# wheel.net
KiCad netlist of a schematic drawn in EAGLE
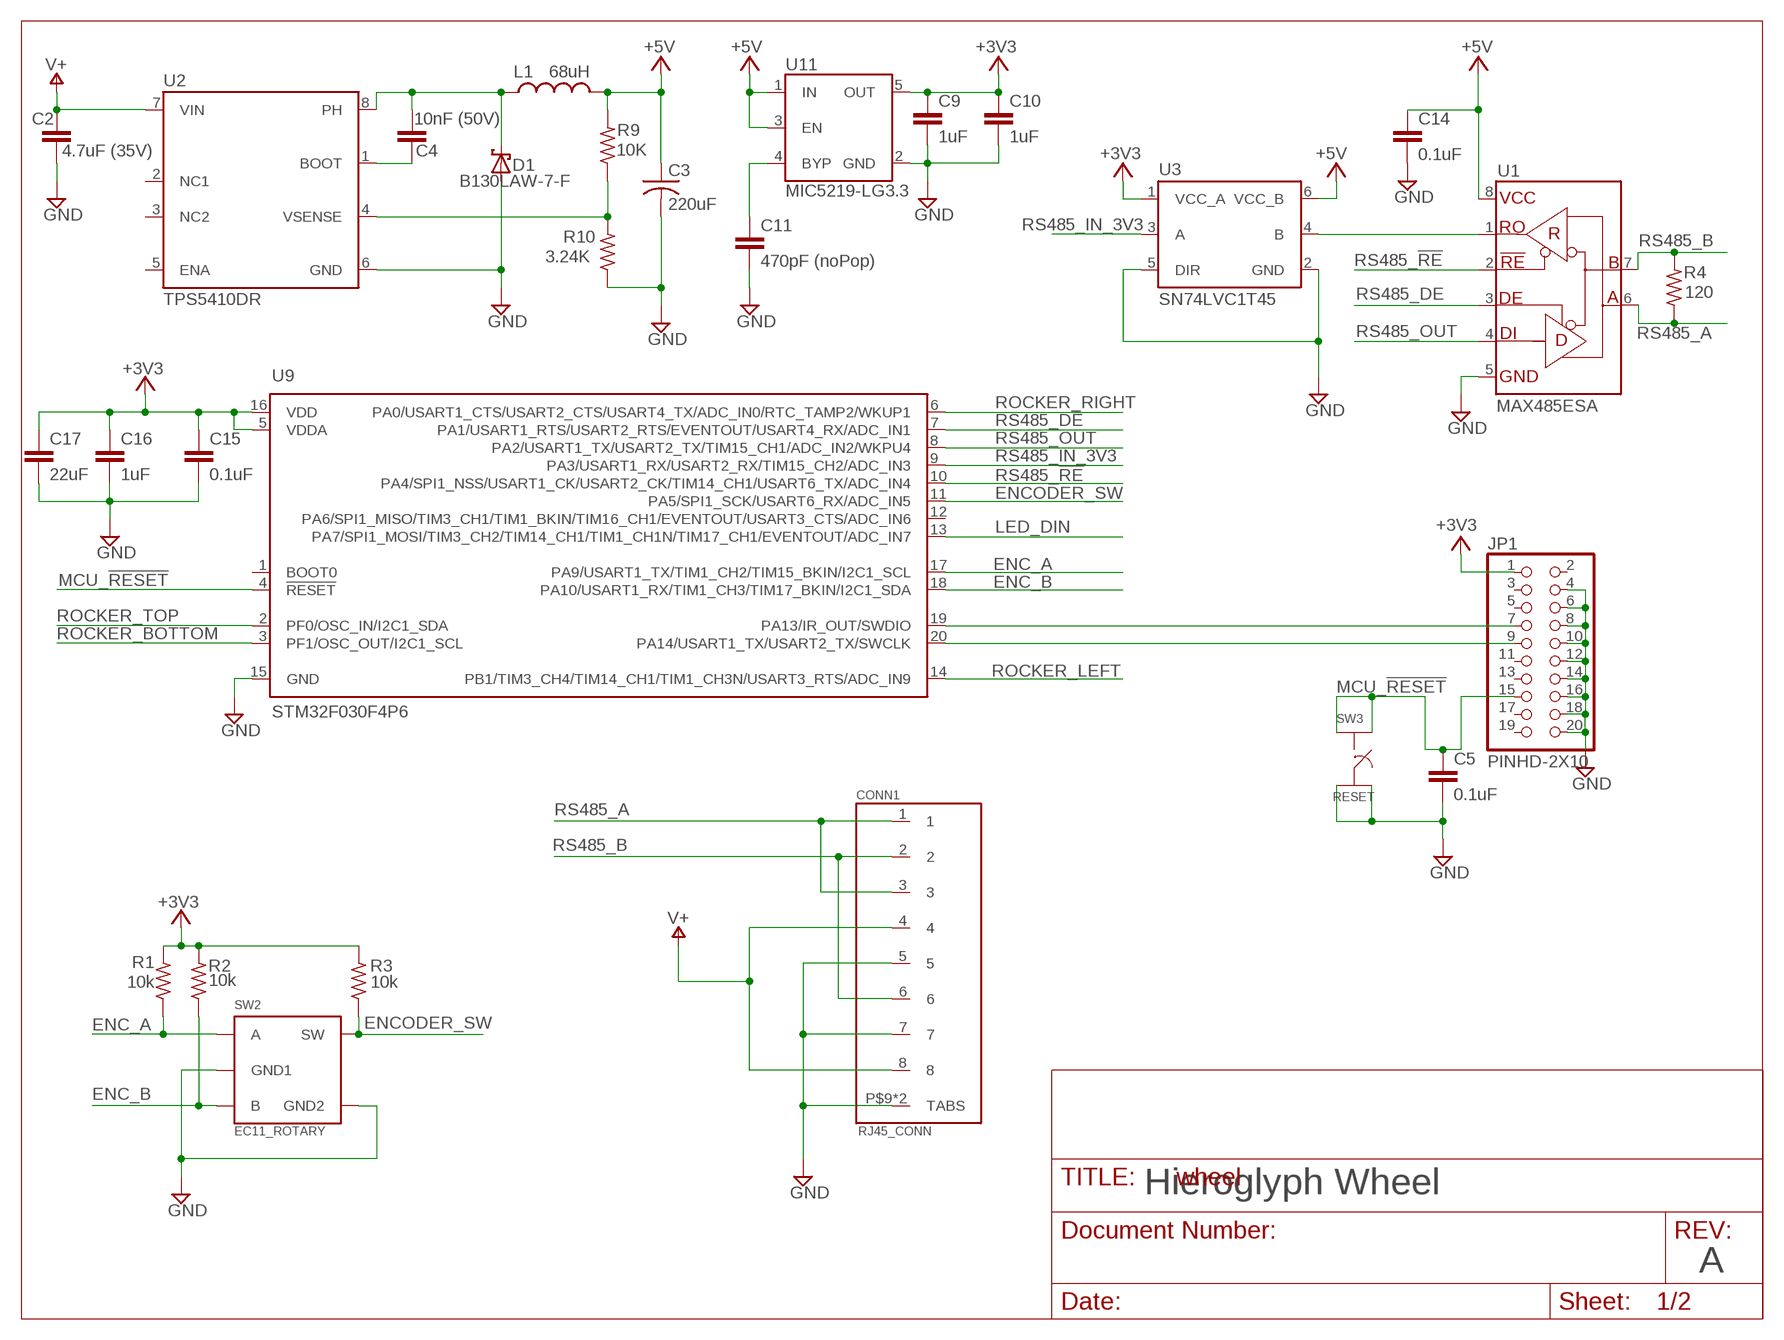
[diagram p0: schematic, sheet 1]
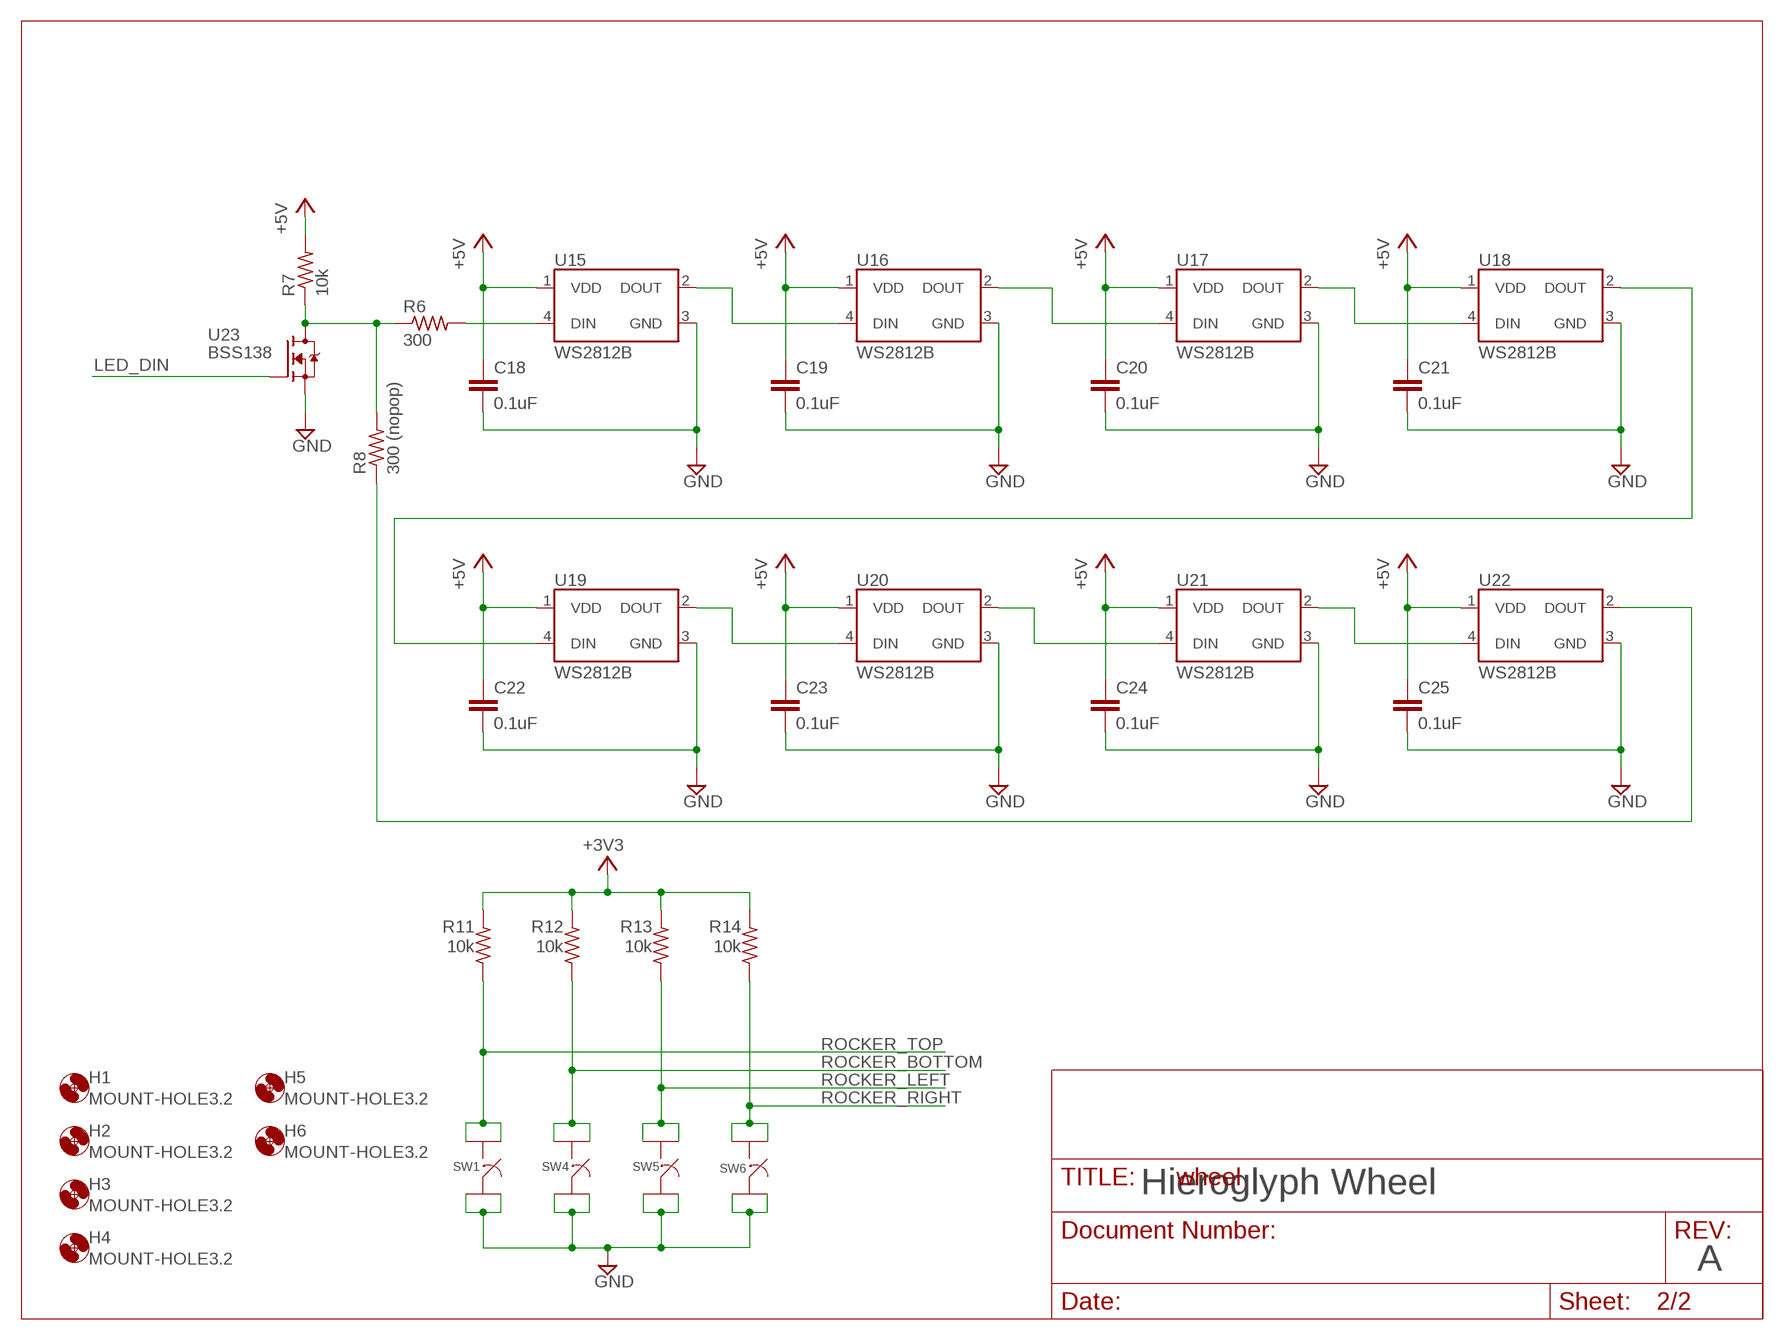
[diagram p1: schematic, sheet 2]

(export (version "E")
  (design (tool "Eeschema 10.0.6"))
  (components
    (comp (ref "C2")
      (value "4.7uF (35V)")
      (footprint "eagle-import:C0805")
      (libsource (lib "eagle-import") (part "C-EUC0805"))
    )
    (comp (ref "C3")
      (value "220uF")
      (footprint "eagle-import:KEMET_D_CAP")
      (libsource (lib "eagle-import") (part "TANT_CAP_D"))
    )
    (comp (ref "C4")
      (value "10nF (50V)")
      (footprint "eagle-import:C0805")
      (libsource (lib "eagle-import") (part "C-EUC0805"))
    )
    (comp (ref "C5")
      (value "0.1uF")
      (footprint "eagle-import:C0805")
      (libsource (lib "eagle-import") (part "C-EUC0805"))
    )
    (comp (ref "C9")
      (value "1uF")
      (footprint "eagle-import:C0805")
      (libsource (lib "eagle-import") (part "C-EUC0805"))
    )
    (comp (ref "C10")
      (value "1uF")
      (footprint "eagle-import:C0805")
      (libsource (lib "eagle-import") (part "C-EUC0805"))
    )
    (comp (ref "C11")
      (value "470pF (noPop)")
      (footprint "eagle-import:C0805")
      (libsource (lib "eagle-import") (part "C-EUC0805"))
    )
    (comp (ref "C14")
      (value "0.1uF")
      (footprint "eagle-import:C0805")
      (libsource (lib "eagle-import") (part "C-EUC0805"))
    )
    (comp (ref "C15")
      (value "0.1uF")
      (footprint "eagle-import:C0805")
      (libsource (lib "eagle-import") (part "C-EUC0805"))
    )
    (comp (ref "C16")
      (value "1uF")
      (footprint "eagle-import:C0805")
      (libsource (lib "eagle-import") (part "C-EUC0805"))
    )
    (comp (ref "C17")
      (value "22uF")
      (footprint "eagle-import:C0805")
      (libsource (lib "eagle-import") (part "C-EUC0805"))
    )
    (comp (ref "CONN1")
      (value "RJ45_CONN")
      (footprint "eagle-import:RJ45_VERT")
      (libsource (lib "eagle-import") (part "RJ45_CONN"))
    )
    (comp (ref "D1")
      (value "B130LAW-7-F")
      (footprint "eagle-import:SOD123")
      (libsource (lib "eagle-import") (part "B130LAW-7-F"))
    )
    (comp (ref "JP1")
      (value "PINHD-2X10")
      (footprint "eagle-import:2X10_W_KEY")
      (libsource (lib "eagle-import") (part "PINHD-2X10"))
    )
    (comp (ref "L1")
      (value "68uH")
      (footprint "eagle-import:CDRH127R")
      (libsource (lib "eagle-import") (part "L_CDRH127"))
    )
    (comp (ref "R1")
      (value "10k")
      (footprint "eagle-import:R0805")
      (libsource (lib "eagle-import") (part "R-US_R0805"))
    )
    (comp (ref "R2")
      (value "10k")
      (footprint "eagle-import:R0805")
      (libsource (lib "eagle-import") (part "R-US_R0805"))
    )
    (comp (ref "R3")
      (value "10k")
      (footprint "eagle-import:R0805")
      (libsource (lib "eagle-import") (part "R-US_R0805"))
    )
    (comp (ref "R4")
      (value "120")
      (footprint "eagle-import:R0805")
      (libsource (lib "eagle-import") (part "R-US_R0805"))
    )
    (comp (ref "R9")
      (value "10K")
      (footprint "eagle-import:R0805")
      (libsource (lib "eagle-import") (part "R-US_R0805"))
    )
    (comp (ref "R10")
      (value "3.24K")
      (footprint "eagle-import:R0805")
      (libsource (lib "eagle-import") (part "R-US_R0805"))
    )
    (comp (ref "SW2")
      (value "EC11_ROTARY")
      (footprint "eagle-import:EC11_ROTARY")
      (libsource (lib "eagle-import") (part "EC11_ROTARY"))
    )
    (comp (ref "SW3")
      (value "RESET")
      (footprint "eagle-import:MOM_SWITCH")
      (libsource (lib "eagle-import") (part "MOM_SWITCH"))
    )
    (comp (ref "U1")
      (value "MAX485ESA")
      (footprint "eagle-import:SO08")
      (libsource (lib "eagle-import") (part "MAX485ESA"))
    )
    (comp (ref "U2")
      (value "TPS5410DR")
      (footprint "eagle-import:SO08")
      (libsource (lib "eagle-import") (part "TPS5410DR"))
    )
    (comp (ref "U3")
      (value "SN74LVC1T45")
      (footprint "eagle-import:SOT23-6")
      (libsource (lib "eagle-import") (part "SN74LVC1T45"))
    )
    (comp (ref "U9")
      (value "STM32F030F4P6")
      (footprint "eagle-import:TSSOP20")
      (libsource (lib "eagle-import") (part "STM32F030F4P6"))
    )
    (comp (ref "U11")
      (value "MIC5219-LG3.3")
      (footprint "eagle-import:SOT23-5")
      (libsource (lib "eagle-import") (part "MIC5219XX"))
    )
    (comp (ref "C18")
      (value "0.1uF")
      (footprint "eagle-import:C0805")
      (libsource (lib "eagle-import") (part "C-EUC0805"))
    )
    (comp (ref "C19")
      (value "0.1uF")
      (footprint "eagle-import:C0805")
      (libsource (lib "eagle-import") (part "C-EUC0805"))
    )
    (comp (ref "C20")
      (value "0.1uF")
      (footprint "eagle-import:C0805")
      (libsource (lib "eagle-import") (part "C-EUC0805"))
    )
    (comp (ref "C21")
      (value "0.1uF")
      (footprint "eagle-import:C0805")
      (libsource (lib "eagle-import") (part "C-EUC0805"))
    )
    (comp (ref "C22")
      (value "0.1uF")
      (footprint "eagle-import:C0805")
      (libsource (lib "eagle-import") (part "C-EUC0805"))
    )
    (comp (ref "C23")
      (value "0.1uF")
      (footprint "eagle-import:C0805")
      (libsource (lib "eagle-import") (part "C-EUC0805"))
    )
    (comp (ref "C24")
      (value "0.1uF")
      (footprint "eagle-import:C0805")
      (libsource (lib "eagle-import") (part "C-EUC0805"))
    )
    (comp (ref "C25")
      (value "0.1uF")
      (footprint "eagle-import:C0805")
      (libsource (lib "eagle-import") (part "C-EUC0805"))
    )
    (comp (ref "H1")
      (value "MOUNT-HOLE3.2")
      (footprint "eagle-import:3,2")
      (libsource (lib "eagle-import") (part "MOUNT-HOLE3.2"))
    )
    (comp (ref "H2")
      (value "MOUNT-HOLE3.2")
      (footprint "eagle-import:3,2")
      (libsource (lib "eagle-import") (part "MOUNT-HOLE3.2"))
    )
    (comp (ref "H3")
      (value "MOUNT-HOLE3.2")
      (footprint "eagle-import:3,2")
      (libsource (lib "eagle-import") (part "MOUNT-HOLE3.2"))
    )
    (comp (ref "H4")
      (value "MOUNT-HOLE3.2")
      (footprint "eagle-import:3,2")
      (libsource (lib "eagle-import") (part "MOUNT-HOLE3.2"))
    )
    (comp (ref "H5")
      (value "MOUNT-HOLE3.2")
      (footprint "eagle-import:3,2")
      (libsource (lib "eagle-import") (part "MOUNT-HOLE3.2"))
    )
    (comp (ref "H6")
      (value "MOUNT-HOLE3.2")
      (footprint "eagle-import:3,2")
      (libsource (lib "eagle-import") (part "MOUNT-HOLE3.2"))
    )
    (comp (ref "R6")
      (value "300")
      (footprint "eagle-import:R0805")
      (libsource (lib "eagle-import") (part "R-US_R0805"))
    )
    (comp (ref "R7")
      (value "10k")
      (footprint "eagle-import:R0805")
      (libsource (lib "eagle-import") (part "R-US_R0805"))
    )
    (comp (ref "R8")
      (value "300 (nopop)")
      (footprint "eagle-import:R0805")
      (libsource (lib "eagle-import") (part "R-US_R0805"))
    )
    (comp (ref "R11")
      (value "10k")
      (footprint "eagle-import:R0805")
      (libsource (lib "eagle-import") (part "R-US_R0805"))
    )
    (comp (ref "R12")
      (value "10k")
      (footprint "eagle-import:R0805")
      (libsource (lib "eagle-import") (part "R-US_R0805"))
    )
    (comp (ref "R13")
      (value "10k")
      (footprint "eagle-import:R0805")
      (libsource (lib "eagle-import") (part "R-US_R0805"))
    )
    (comp (ref "R14")
      (value "10k")
      (footprint "eagle-import:R0805")
      (libsource (lib "eagle-import") (part "R-US_R0805"))
    )
    (comp (ref "SW1")
      (value "MOM_SWITCH")
      (footprint "eagle-import:MOM_SWITCH")
      (libsource (lib "eagle-import") (part "MOM_SWITCH"))
    )
    (comp (ref "SW4")
      (value "MOM_SWITCH")
      (footprint "eagle-import:MOM_SWITCH")
      (libsource (lib "eagle-import") (part "MOM_SWITCH"))
    )
    (comp (ref "SW5")
      (value "MOM_SWITCH")
      (footprint "eagle-import:MOM_SWITCH")
      (libsource (lib "eagle-import") (part "MOM_SWITCH"))
    )
    (comp (ref "SW6")
      (value "MOM_SWITCH")
      (footprint "eagle-import:MOM_SWITCH")
      (libsource (lib "eagle-import") (part "MOM_SWITCH"))
    )
    (comp (ref "U15")
      (value "WS2812B")
      (footprint "eagle-import:WS2812B")
      (libsource (lib "eagle-import") (part "WS2812B"))
    )
    (comp (ref "U16")
      (value "WS2812B")
      (footprint "eagle-import:WS2812B")
      (libsource (lib "eagle-import") (part "WS2812B"))
    )
    (comp (ref "U17")
      (value "WS2812B")
      (footprint "eagle-import:WS2812B")
      (libsource (lib "eagle-import") (part "WS2812B"))
    )
    (comp (ref "U18")
      (value "WS2812B")
      (footprint "eagle-import:WS2812B")
      (libsource (lib "eagle-import") (part "WS2812B"))
    )
    (comp (ref "U19")
      (value "WS2812B")
      (footprint "eagle-import:WS2812B")
      (libsource (lib "eagle-import") (part "WS2812B"))
    )
    (comp (ref "U20")
      (value "WS2812B")
      (footprint "eagle-import:WS2812B")
      (libsource (lib "eagle-import") (part "WS2812B"))
    )
    (comp (ref "U21")
      (value "WS2812B")
      (footprint "eagle-import:WS2812B")
      (libsource (lib "eagle-import") (part "WS2812B"))
    )
    (comp (ref "U22")
      (value "WS2812B")
      (footprint "eagle-import:WS2812B")
      (libsource (lib "eagle-import") (part "WS2812B"))
    )
    (comp (ref "U23")
      (value "BSS138")
      (footprint "eagle-import:SOT23")
      (libsource (lib "eagle-import") (part "BSS138"))
    )
  )
  (nets
    (net (code "1") (name "+3V3") (class "Default")
      (node (ref "C10") (pin "1") (pinfunction "1_1") (pintype "passive"))
      (node (ref "C15") (pin "1") (pinfunction "1_1") (pintype "passive"))
      (node (ref "C16") (pin "1") (pinfunction "1_1") (pintype "passive"))
      (node (ref "C17") (pin "1") (pinfunction "1_1") (pintype "passive"))
      (node (ref "C9") (pin "1") (pinfunction "1_1") (pintype "passive"))
      (node (ref "JP1") (pin "1") (pinfunction "1_1") (pintype "passive"))
      (node (ref "R1") (pin "2") (pinfunction "2_2") (pintype "passive"))
      (node (ref "R11") (pin "2") (pinfunction "2_2") (pintype "passive"))
      (node (ref "R12") (pin "2") (pinfunction "2_2") (pintype "passive"))
      (node (ref "R13") (pin "2") (pinfunction "2_2") (pintype "passive"))
      (node (ref "R14") (pin "2") (pinfunction "2_2") (pintype "passive"))
      (node (ref "R2") (pin "2") (pinfunction "2_2") (pintype "passive"))
      (node (ref "R3") (pin "2") (pinfunction "2_2") (pintype "passive"))
      (node (ref "U11") (pin "5") (pinfunction "OUT_5") (pintype "power_in"))
      (node (ref "U3") (pin "1") (pinfunction "VCC_A_1") (pintype "power_in"))
      (node (ref "U9") (pin "16") (pinfunction "VDD_16") (pintype "power_in"))
      (node (ref "U9") (pin "5") (pinfunction "VDDA_5") (pintype "power_in"))
    )
    (net (code "2") (name "+5V") (class "Default")
      (node (ref "C14") (pin "1") (pinfunction "1_1") (pintype "passive"))
      (node (ref "C18") (pin "1") (pinfunction "1_1") (pintype "passive"))
      (node (ref "C19") (pin "1") (pinfunction "1_1") (pintype "passive"))
      (node (ref "C20") (pin "1") (pinfunction "1_1") (pintype "passive"))
      (node (ref "C21") (pin "1") (pinfunction "1_1") (pintype "passive"))
      (node (ref "C22") (pin "1") (pinfunction "1_1") (pintype "passive"))
      (node (ref "C23") (pin "1") (pinfunction "1_1") (pintype "passive"))
      (node (ref "C24") (pin "1") (pinfunction "1_1") (pintype "passive"))
      (node (ref "C25") (pin "1") (pinfunction "1_1") (pintype "passive"))
      (node (ref "C3") (pin "+") (pinfunction "1_+") (pintype "passive"))
      (node (ref "L1") (pin "P$2") (pinfunction "2_P$2") (pintype "passive"))
      (node (ref "R7") (pin "2") (pinfunction "2_2") (pintype "passive"))
      (node (ref "R9") (pin "2") (pinfunction "2_2") (pintype "passive"))
      (node (ref "U1") (pin "8") (pinfunction "VCC_8") (pintype "power_in"))
      (node (ref "U11") (pin "1") (pinfunction "IN_1") (pintype "power_in"))
      (node (ref "U11") (pin "3") (pinfunction "EN_3") (pintype "input"))
      (node (ref "U15") (pin "1") (pinfunction "VDD_1") (pintype "power_in"))
      (node (ref "U16") (pin "1") (pinfunction "VDD_1") (pintype "power_in"))
      (node (ref "U17") (pin "1") (pinfunction "VDD_1") (pintype "power_in"))
      (node (ref "U18") (pin "1") (pinfunction "VDD_1") (pintype "power_in"))
      (node (ref "U19") (pin "1") (pinfunction "VDD_1") (pintype "power_in"))
      (node (ref "U20") (pin "1") (pinfunction "VDD_1") (pintype "power_in"))
      (node (ref "U21") (pin "1") (pinfunction "VDD_1") (pintype "power_in"))
      (node (ref "U22") (pin "1") (pinfunction "VDD_1") (pintype "power_in"))
      (node (ref "U3") (pin "6") (pinfunction "VCC_B_6") (pintype "power_in"))
    )
    (net (code "3") (name "ENCODER_SW") (class "Default")
      (node (ref "R3") (pin "1") (pinfunction "1_1") (pintype "passive"))
      (node (ref "SW2") (pin "SW") (pinfunction "SW_SW") (pintype "bidirectional"))
      (node (ref "U9") (pin "11") (pinfunction "PA5/SPI1_SCK/USART6_RX/ADC_IN5_11") (pintype "bidirectional"))
    )
    (net (code "4") (name "ENC_A") (class "Default")
      (node (ref "R1") (pin "1") (pinfunction "1_1") (pintype "passive"))
      (node (ref "SW2") (pin "A") (pinfunction "A_A") (pintype "bidirectional"))
      (node (ref "U9") (pin "17") (pinfunction "PA9/USART1_TX/TIM1_CH2/TIM15_BKIN/I2C1_SCL_17") (pintype "bidirectional"))
    )
    (net (code "5") (name "ENC_B") (class "Default")
      (node (ref "R2") (pin "1") (pinfunction "1_1") (pintype "passive"))
      (node (ref "SW2") (pin "B") (pinfunction "B_B") (pintype "bidirectional"))
      (node (ref "U9") (pin "18") (pinfunction "PA10/USART1_RX/TIM1_CH3/TIM17_BKIN/I2C1_SDA_18") (pintype "bidirectional"))
    )
    (net (code "6") (name "GND") (class "Default")
      (node (ref "C10") (pin "2") (pinfunction "2_2") (pintype "passive"))
      (node (ref "C11") (pin "2") (pinfunction "2_2") (pintype "passive"))
      (node (ref "C14") (pin "2") (pinfunction "2_2") (pintype "passive"))
      (node (ref "C15") (pin "2") (pinfunction "2_2") (pintype "passive"))
      (node (ref "C16") (pin "2") (pinfunction "2_2") (pintype "passive"))
      (node (ref "C17") (pin "2") (pinfunction "2_2") (pintype "passive"))
      (node (ref "C18") (pin "2") (pinfunction "2_2") (pintype "passive"))
      (node (ref "C19") (pin "2") (pinfunction "2_2") (pintype "passive"))
      (node (ref "C2") (pin "2") (pinfunction "2_2") (pintype "passive"))
      (node (ref "C20") (pin "2") (pinfunction "2_2") (pintype "passive"))
      (node (ref "C21") (pin "2") (pinfunction "2_2") (pintype "passive"))
      (node (ref "C22") (pin "2") (pinfunction "2_2") (pintype "passive"))
      (node (ref "C23") (pin "2") (pinfunction "2_2") (pintype "passive"))
      (node (ref "C24") (pin "2") (pinfunction "2_2") (pintype "passive"))
      (node (ref "C25") (pin "2") (pinfunction "2_2") (pintype "passive"))
      (node (ref "C3") (pin "-") (pinfunction "2_-") (pintype "passive"))
      (node (ref "C5") (pin "2") (pinfunction "2_2") (pintype "passive"))
      (node (ref "C9") (pin "2") (pinfunction "2_2") (pintype "passive"))
      (node (ref "CONN1") (pin "5") (pinfunction "5_5") (pintype "bidirectional"))
      (node (ref "CONN1") (pin "7") (pinfunction "7_7") (pintype "bidirectional"))
      (node (ref "CONN1") (pin "P$10") (pinfunction "TABS_P$10") (pintype "bidirectional"))
      (node (ref "CONN1") (pin "P$9") (pinfunction "TABS_P$9") (pintype "bidirectional"))
      (node (ref "D1") (pin "A") (pinfunction "A_A") (pintype "passive"))
      (node (ref "JP1") (pin "10") (pinfunction "10_10") (pintype "passive"))
      (node (ref "JP1") (pin "12") (pinfunction "12_12") (pintype "passive"))
      (node (ref "JP1") (pin "14") (pinfunction "14_14") (pintype "passive"))
      (node (ref "JP1") (pin "16") (pinfunction "16_16") (pintype "passive"))
      (node (ref "JP1") (pin "18") (pinfunction "18_18") (pintype "passive"))
      (node (ref "JP1") (pin "20") (pinfunction "20_20") (pintype "passive"))
      (node (ref "JP1") (pin "4") (pinfunction "4_4") (pintype "passive"))
      (node (ref "JP1") (pin "6") (pinfunction "6_6") (pintype "passive"))
      (node (ref "JP1") (pin "8") (pinfunction "8_8") (pintype "passive"))
      (node (ref "R10") (pin "1") (pinfunction "1_1") (pintype "passive"))
      (node (ref "SW1") (pin "P$3") (pinfunction "3_P$3") (pintype "bidirectional"))
      (node (ref "SW1") (pin "P$4") (pinfunction "4_P$4") (pintype "bidirectional"))
      (node (ref "SW2") (pin "C") (pinfunction "GND1_C") (pintype "bidirectional"))
      (node (ref "SW2") (pin "D") (pinfunction "GND2_D") (pintype "bidirectional"))
      (node (ref "SW3") (pin "P$3") (pinfunction "3_P$3") (pintype "bidirectional"))
      (node (ref "SW3") (pin "P$4") (pinfunction "4_P$4") (pintype "bidirectional"))
      (node (ref "SW4") (pin "P$3") (pinfunction "3_P$3") (pintype "bidirectional"))
      (node (ref "SW4") (pin "P$4") (pinfunction "4_P$4") (pintype "bidirectional"))
      (node (ref "SW5") (pin "P$3") (pinfunction "3_P$3") (pintype "bidirectional"))
      (node (ref "SW5") (pin "P$4") (pinfunction "4_P$4") (pintype "bidirectional"))
      (node (ref "SW6") (pin "P$3") (pinfunction "3_P$3") (pintype "bidirectional"))
      (node (ref "SW6") (pin "P$4") (pinfunction "4_P$4") (pintype "bidirectional"))
      (node (ref "U1") (pin "5") (pinfunction "GND_5") (pintype "power_in"))
      (node (ref "U11") (pin "2") (pinfunction "GND_2") (pintype "power_in"))
      (node (ref "U15") (pin "3") (pinfunction "GND_3") (pintype "power_in"))
      (node (ref "U16") (pin "3") (pinfunction "GND_3") (pintype "power_in"))
      (node (ref "U17") (pin "3") (pinfunction "GND_3") (pintype "power_in"))
      (node (ref "U18") (pin "3") (pinfunction "GND_3") (pintype "power_in"))
      (node (ref "U19") (pin "3") (pinfunction "GND_3") (pintype "power_in"))
      (node (ref "U2") (pin "6") (pinfunction "GND_6") (pintype "bidirectional"))
      (node (ref "U20") (pin "3") (pinfunction "GND_3") (pintype "power_in"))
      (node (ref "U21") (pin "3") (pinfunction "GND_3") (pintype "power_in"))
      (node (ref "U22") (pin "3") (pinfunction "GND_3") (pintype "power_in"))
      (node (ref "U23") (pin "2") (pinfunction "S_2") (pintype "passive"))
      (node (ref "U3") (pin "2") (pinfunction "GND_2") (pintype "power_in"))
      (node (ref "U3") (pin "5") (pinfunction "DIR_5") (pintype "input"))
      (node (ref "U9") (pin "15") (pinfunction "GND_15") (pintype "power_in"))
    )
    (net (code "7") (name "LED_DIN") (class "Default")
      (node (ref "U23") (pin "1") (pinfunction "G_1") (pintype "passive"))
      (node (ref "U9") (pin "13") (pinfunction "PA7/SPI1_MOSI/TIM3_CH2/TIM14_CH1/TIM1_CH1N/TIM17_CH1/EVENTOUT/ADC_IN7_13") (pintype "bidirectional"))
    )
    (net (code "8") (name "MCU_~{RESET}") (class "Default")
      (node (ref "C5") (pin "1") (pinfunction "1_1") (pintype "passive"))
      (node (ref "JP1") (pin "15") (pinfunction "15_15") (pintype "passive"))
      (node (ref "SW3") (pin "P$1") (pinfunction "1_P$1") (pintype "bidirectional"))
      (node (ref "SW3") (pin "P$2") (pinfunction "2_P$2") (pintype "bidirectional"))
      (node (ref "U9") (pin "4") (pinfunction "~{RESET}_4") (pintype "input"))
    )
    (net (code "9") (name "Net-(U1-RO)") (class "Default")
      (node (ref "U1") (pin "1") (pinfunction "RO_1") (pintype "output"))
      (node (ref "U3") (pin "4") (pinfunction "B_4") (pintype "bidirectional"))
    )
    (net (code "10") (name "Net-(U2-BOOT)") (class "Default")
      (node (ref "C4") (pin "2") (pinfunction "2_2") (pintype "passive"))
      (node (ref "U2") (pin "1") (pinfunction "BOOT_1") (pintype "bidirectional"))
    )
    (net (code "11") (name "Net-(U2-PH)") (class "Default")
      (node (ref "C4") (pin "1") (pinfunction "1_1") (pintype "passive"))
      (node (ref "D1") (pin "C") (pinfunction "C_C") (pintype "passive"))
      (node (ref "L1") (pin "1") (pinfunction "1_1") (pintype "passive"))
      (node (ref "U2") (pin "8") (pinfunction "PH_8") (pintype "bidirectional"))
    )
    (net (code "12") (name "Net-(U2-VSENSE)") (class "Default")
      (node (ref "R10") (pin "2") (pinfunction "2_2") (pintype "passive"))
      (node (ref "R9") (pin "1") (pinfunction "1_1") (pintype "passive"))
      (node (ref "U2") (pin "4") (pinfunction "VSENSE_4") (pintype "bidirectional"))
    )
    (net (code "13") (name "Net-(U9-PA13{slash}IR_OUT{slash}SWDIO)") (class "Default")
      (node (ref "JP1") (pin "7") (pinfunction "7_7") (pintype "passive"))
      (node (ref "U9") (pin "19") (pinfunction "PA13/IR_OUT/SWDIO_19") (pintype "bidirectional"))
    )
    (net (code "14") (name "Net-(U9-PA14{slash}USART1_TX{slash}USART2_TX{slash}SWCLK)") (class "Default")
      (node (ref "JP1") (pin "9") (pinfunction "9_9") (pintype "passive"))
      (node (ref "U9") (pin "20") (pinfunction "PA14/USART1_TX/USART2_TX/SWCLK_20") (pintype "bidirectional"))
    )
    (net (code "15") (name "Net-(U11-BYP)") (class "Default")
      (node (ref "C11") (pin "1") (pinfunction "1_1") (pintype "passive"))
      (node (ref "U11") (pin "4") (pinfunction "BYP_4") (pintype "passive"))
    )
    (net (code "16") (name "Net-(U15-DIN)") (class "Default")
      (node (ref "R6") (pin "2") (pinfunction "2_2") (pintype "passive"))
      (node (ref "U15") (pin "4") (pinfunction "DIN_4") (pintype "input"))
    )
    (net (code "17") (name "Net-(U15-DOUT)") (class "Default")
      (node (ref "U15") (pin "2") (pinfunction "DOUT_2") (pintype "output"))
      (node (ref "U16") (pin "4") (pinfunction "DIN_4") (pintype "input"))
    )
    (net (code "18") (name "Net-(U16-DOUT)") (class "Default")
      (node (ref "U16") (pin "2") (pinfunction "DOUT_2") (pintype "output"))
      (node (ref "U17") (pin "4") (pinfunction "DIN_4") (pintype "input"))
    )
    (net (code "19") (name "Net-(U17-DOUT)") (class "Default")
      (node (ref "U17") (pin "2") (pinfunction "DOUT_2") (pintype "output"))
      (node (ref "U18") (pin "4") (pinfunction "DIN_4") (pintype "input"))
    )
    (net (code "20") (name "Net-(U18-DOUT)") (class "Default")
      (node (ref "U18") (pin "2") (pinfunction "DOUT_2") (pintype "output"))
      (node (ref "U19") (pin "4") (pinfunction "DIN_4") (pintype "input"))
    )
    (net (code "21") (name "Net-(U19-DOUT)") (class "Default")
      (node (ref "U19") (pin "2") (pinfunction "DOUT_2") (pintype "output"))
      (node (ref "U20") (pin "4") (pinfunction "DIN_4") (pintype "input"))
    )
    (net (code "22") (name "Net-(U20-DOUT)") (class "Default")
      (node (ref "U20") (pin "2") (pinfunction "DOUT_2") (pintype "output"))
      (node (ref "U21") (pin "4") (pinfunction "DIN_4") (pintype "input"))
    )
    (net (code "23") (name "Net-(U21-DOUT)") (class "Default")
      (node (ref "U21") (pin "2") (pinfunction "DOUT_2") (pintype "output"))
      (node (ref "U22") (pin "4") (pinfunction "DIN_4") (pintype "input"))
    )
    (net (code "24") (name "Net-(U22-DOUT)") (class "Default")
      (node (ref "R8") (pin "1") (pinfunction "1_1") (pintype "passive"))
      (node (ref "U22") (pin "2") (pinfunction "DOUT_2") (pintype "output"))
    )
    (net (code "25") (name "Net-(U23-D)") (class "Default")
      (node (ref "R6") (pin "1") (pinfunction "1_1") (pintype "passive"))
      (node (ref "R7") (pin "1") (pinfunction "1_1") (pintype "passive"))
      (node (ref "R8") (pin "2") (pinfunction "2_2") (pintype "passive"))
      (node (ref "U23") (pin "3") (pinfunction "D_3") (pintype "passive"))
    )
    (net (code "26") (name "ROCKER_BOTTOM") (class "Default")
      (node (ref "R12") (pin "1") (pinfunction "1_1") (pintype "passive"))
      (node (ref "SW4") (pin "P$1") (pinfunction "1_P$1") (pintype "bidirectional"))
      (node (ref "SW4") (pin "P$2") (pinfunction "2_P$2") (pintype "bidirectional"))
      (node (ref "U9") (pin "3") (pinfunction "PF1/OSC_OUT/I2C1_SCL_3") (pintype "bidirectional"))
    )
    (net (code "27") (name "ROCKER_LEFT") (class "Default")
      (node (ref "R13") (pin "1") (pinfunction "1_1") (pintype "passive"))
      (node (ref "SW5") (pin "P$1") (pinfunction "1_P$1") (pintype "bidirectional"))
      (node (ref "SW5") (pin "P$2") (pinfunction "2_P$2") (pintype "bidirectional"))
      (node (ref "U9") (pin "14") (pinfunction "PB1/TIM3_CH4/TIM14_CH1/TIM1_CH3N/USART3_RTS/ADC_IN9_14") (pintype "bidirectional"))
    )
    (net (code "28") (name "ROCKER_RIGHT") (class "Default")
      (node (ref "R14") (pin "1") (pinfunction "1_1") (pintype "passive"))
      (node (ref "SW6") (pin "P$1") (pinfunction "1_P$1") (pintype "bidirectional"))
      (node (ref "SW6") (pin "P$2") (pinfunction "2_P$2") (pintype "bidirectional"))
      (node (ref "U9") (pin "6") (pinfunction "PA0/USART1_CTS/USART2_CTS/USART4_TX/ADC_IN0/RTC_TAMP2/WKUP1_6") (pintype "bidirectional"))
    )
    (net (code "29") (name "ROCKER_TOP") (class "Default")
      (node (ref "R11") (pin "1") (pinfunction "1_1") (pintype "passive"))
      (node (ref "SW1") (pin "P$1") (pinfunction "1_P$1") (pintype "bidirectional"))
      (node (ref "SW1") (pin "P$2") (pinfunction "2_P$2") (pintype "bidirectional"))
      (node (ref "U9") (pin "2") (pinfunction "PF0/OSC_IN/I2C1_SDA_2") (pintype "bidirectional"))
    )
    (net (code "30") (name "RS485_A") (class "Default")
      (node (ref "CONN1") (pin "1") (pinfunction "1_1") (pintype "bidirectional"))
      (node (ref "CONN1") (pin "3") (pinfunction "3_3") (pintype "bidirectional"))
      (node (ref "R4") (pin "1") (pinfunction "1_1") (pintype "passive"))
      (node (ref "U1") (pin "6") (pinfunction "A_6") (pintype "bidirectional"))
    )
    (net (code "31") (name "RS485_B") (class "Default")
      (node (ref "CONN1") (pin "2") (pinfunction "2_2") (pintype "bidirectional"))
      (node (ref "CONN1") (pin "6") (pinfunction "6_6") (pintype "bidirectional"))
      (node (ref "R4") (pin "2") (pinfunction "2_2") (pintype "passive"))
      (node (ref "U1") (pin "7") (pinfunction "B_7") (pintype "bidirectional"))
    )
    (net (code "32") (name "RS485_DE") (class "Default")
      (node (ref "U1") (pin "3") (pinfunction "DE_3") (pintype "input"))
      (node (ref "U9") (pin "7") (pinfunction "PA1/USART1_RTS/USART2_RTS/EVENTOUT/USART4_RX/ADC_IN1_7") (pintype "bidirectional"))
    )
    (net (code "33") (name "RS485_IN_3V3") (class "Default")
      (node (ref "U3") (pin "3") (pinfunction "A_3") (pintype "bidirectional"))
      (node (ref "U9") (pin "9") (pinfunction "PA3/USART1_RX/USART2_RX/TIM15_CH2/ADC_IN3_9") (pintype "bidirectional"))
    )
    (net (code "34") (name "RS485_OUT") (class "Default")
      (node (ref "U1") (pin "4") (pinfunction "DI_4") (pintype "input"))
      (node (ref "U9") (pin "8") (pinfunction "PA2/USART1_TX/USART2_TX/TIM15_CH1/ADC_IN2/WKPU4_8") (pintype "bidirectional"))
    )
    (net (code "35") (name "RS485_~{RE}") (class "Default")
      (node (ref "U1") (pin "2") (pinfunction "~{RE}_2") (pintype "output"))
      (node (ref "U9") (pin "10") (pinfunction "PA4/SPI1_NSS/USART1_CK/USART2_CK/TIM14_CH1/USART6_TX/ADC_IN4_10") (pintype "bidirectional"))
    )
    (net (code "36") (name "V+") (class "Default")
      (node (ref "C2") (pin "1") (pinfunction "1_1") (pintype "passive"))
      (node (ref "CONN1") (pin "4") (pinfunction "4_4") (pintype "bidirectional"))
      (node (ref "CONN1") (pin "8") (pinfunction "8_8") (pintype "bidirectional"))
      (node (ref "U2") (pin "7") (pinfunction "VIN_7") (pintype "bidirectional"))
    )
    (net (code "37") (name "unconnected-(JP1-Pad2)") (class "Default")
      (node (ref "JP1") (pin "2") (pinfunction "2_2") (pintype "passive"))
    )
    (net (code "38") (name "unconnected-(JP1-Pad3)") (class "Default")
      (node (ref "JP1") (pin "3") (pinfunction "3_3") (pintype "passive"))
    )
    (net (code "39") (name "unconnected-(JP1-Pad5)") (class "Default")
      (node (ref "JP1") (pin "5") (pinfunction "5_5") (pintype "passive"))
    )
    (net (code "40") (name "unconnected-(JP1-Pad11)") (class "Default")
      (node (ref "JP1") (pin "11") (pinfunction "11_11") (pintype "passive"))
    )
    (net (code "41") (name "unconnected-(JP1-Pad13)") (class "Default")
      (node (ref "JP1") (pin "13") (pinfunction "13_13") (pintype "passive"))
    )
    (net (code "42") (name "unconnected-(JP1-Pad17)") (class "Default")
      (node (ref "JP1") (pin "17") (pinfunction "17_17") (pintype "passive"))
    )
    (net (code "43") (name "unconnected-(JP1-Pad19)") (class "Default")
      (node (ref "JP1") (pin "19") (pinfunction "19_19") (pintype "passive"))
    )
    (net (code "44") (name "unconnected-(U2-ENA-Pad5)") (class "Default")
      (node (ref "U2") (pin "5") (pinfunction "ENA_5") (pintype "bidirectional"))
    )
    (net (code "45") (name "unconnected-(U2-NC1-Pad2)") (class "Default")
      (node (ref "U2") (pin "2") (pinfunction "NC1_2") (pintype "bidirectional"))
    )
    (net (code "46") (name "unconnected-(U2-NC2-Pad3)") (class "Default")
      (node (ref "U2") (pin "3") (pinfunction "NC2_3") (pintype "bidirectional"))
    )
    (net (code "47") (name "unconnected-(U9-BOOT0-Pad1)") (class "Default")
      (node (ref "U9") (pin "1") (pinfunction "BOOT0_1") (pintype "bidirectional"))
    )
    (net (code "48") (name "unconnected-(U9-PA6{slash}SPI1_MISO{slash}TIM3_CH1{slash}TIM1_BKIN{slash}TIM16_CH1{slash}EVENTOUT{slash}USART3_CTS{slash}ADC_IN6-Pad12)") (class "Default")
      (node (ref "U9") (pin "12") (pinfunction "PA6/SPI1_MISO/TIM3_CH1/TIM1_BKIN/TIM16_CH1/EVENTOUT/USART3_CTS/ADC_IN6_12") (pintype "bidirectional"))
    )
  )
)
